# H2_V5_2_schh.net
KiCad netlist of a schematic drawn in EAGLE
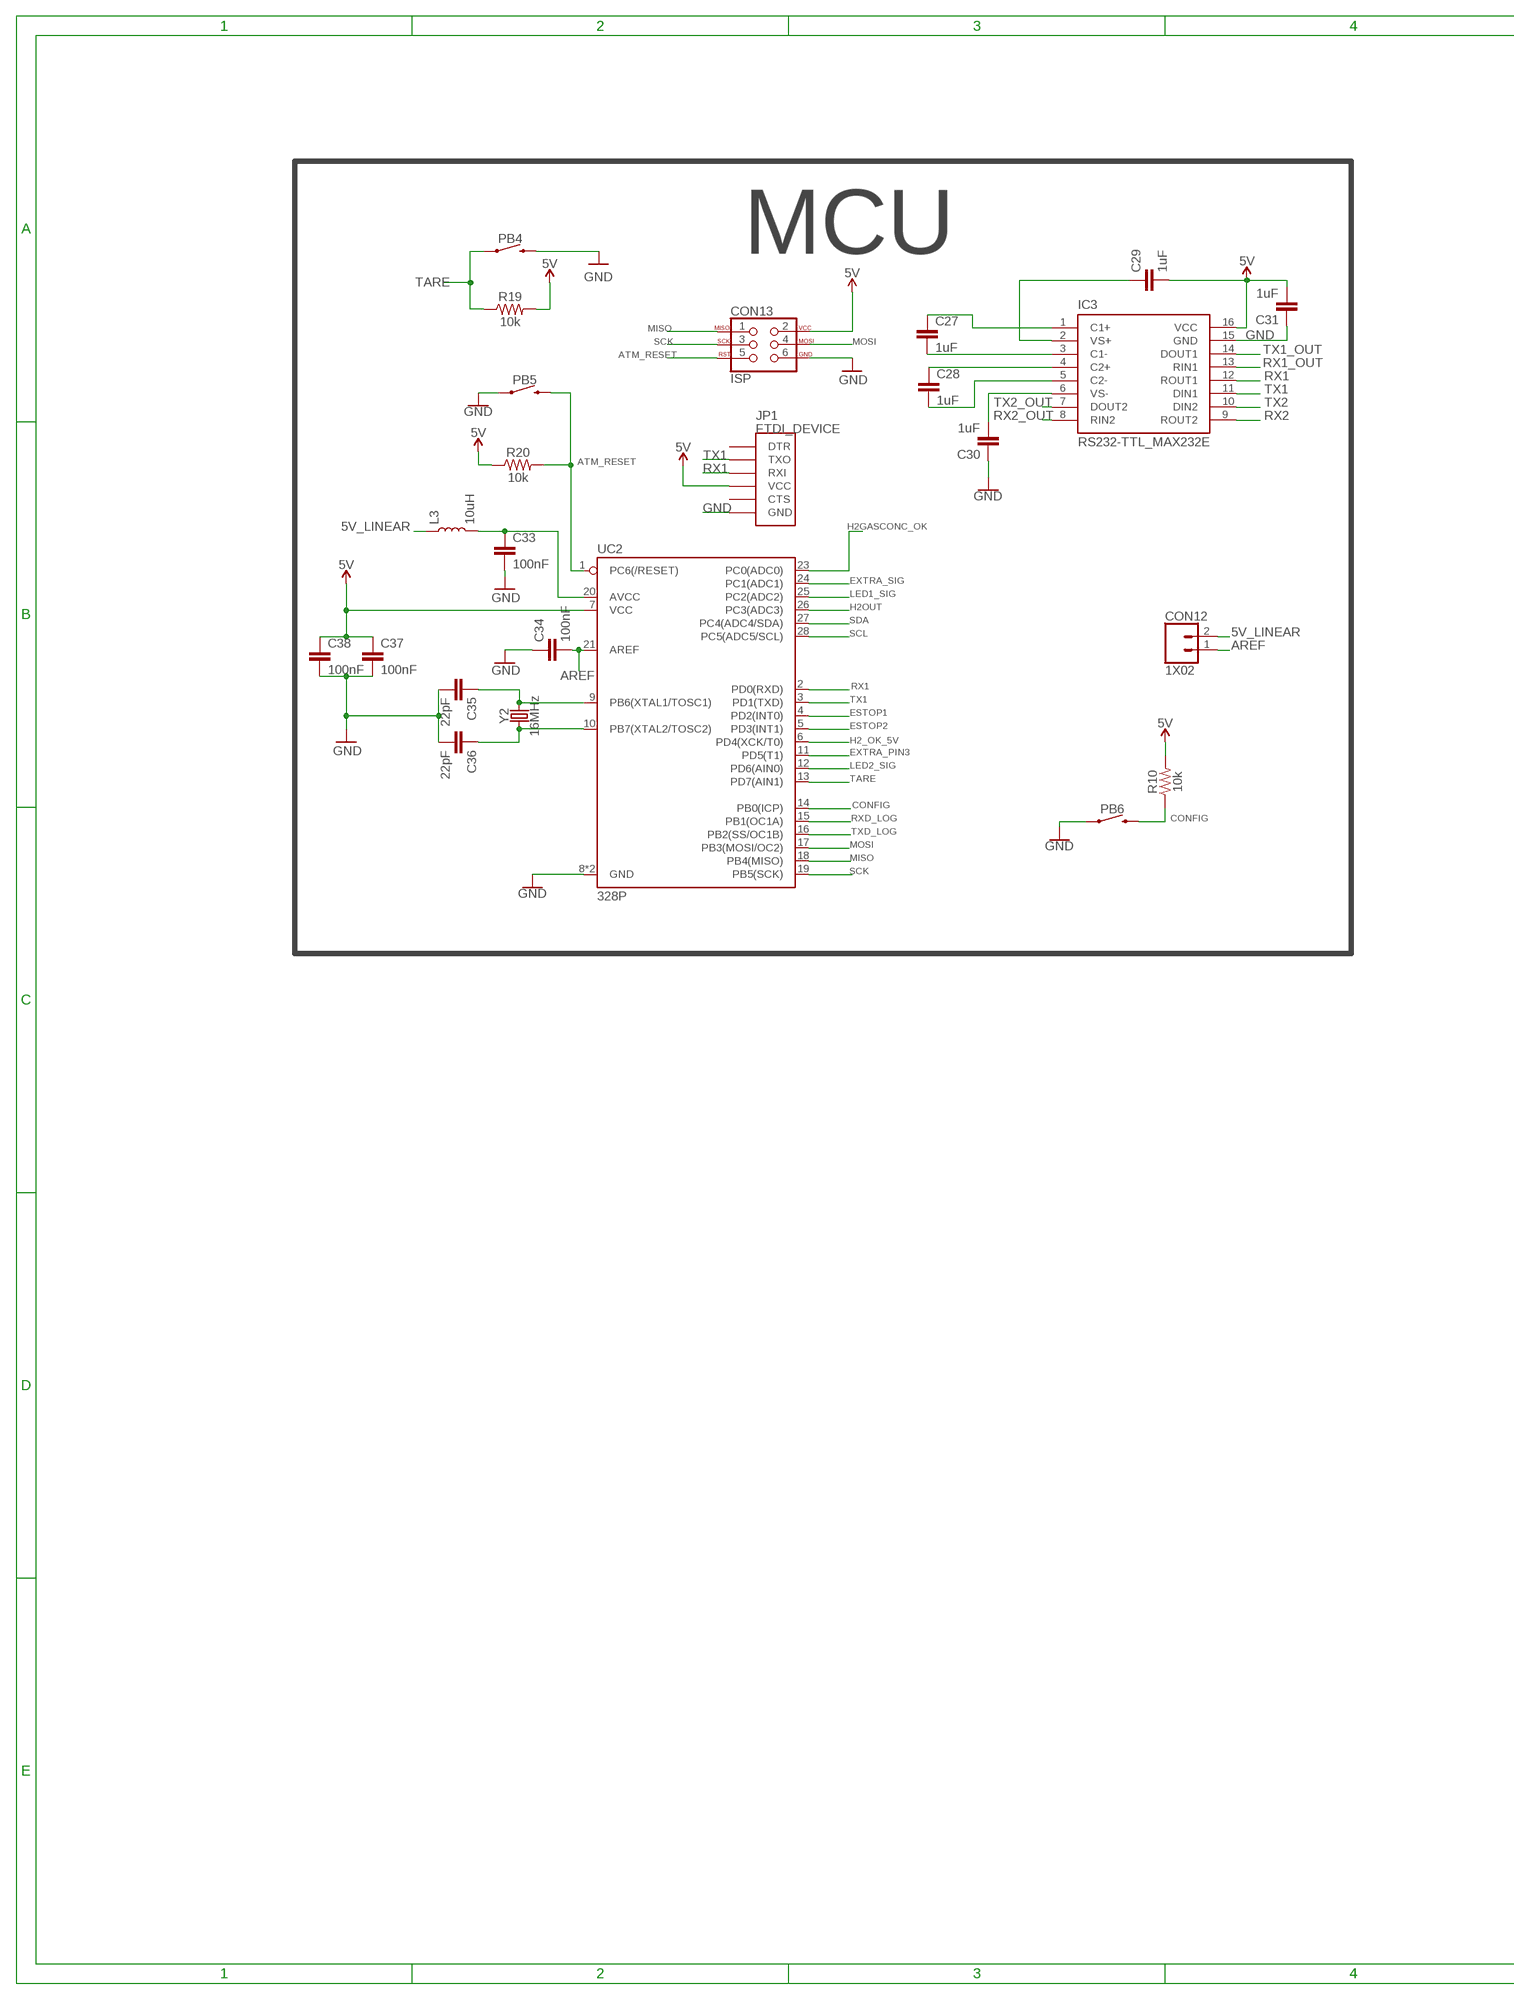
[diagram p0: schematic, sheet 1, part 1 of 2]
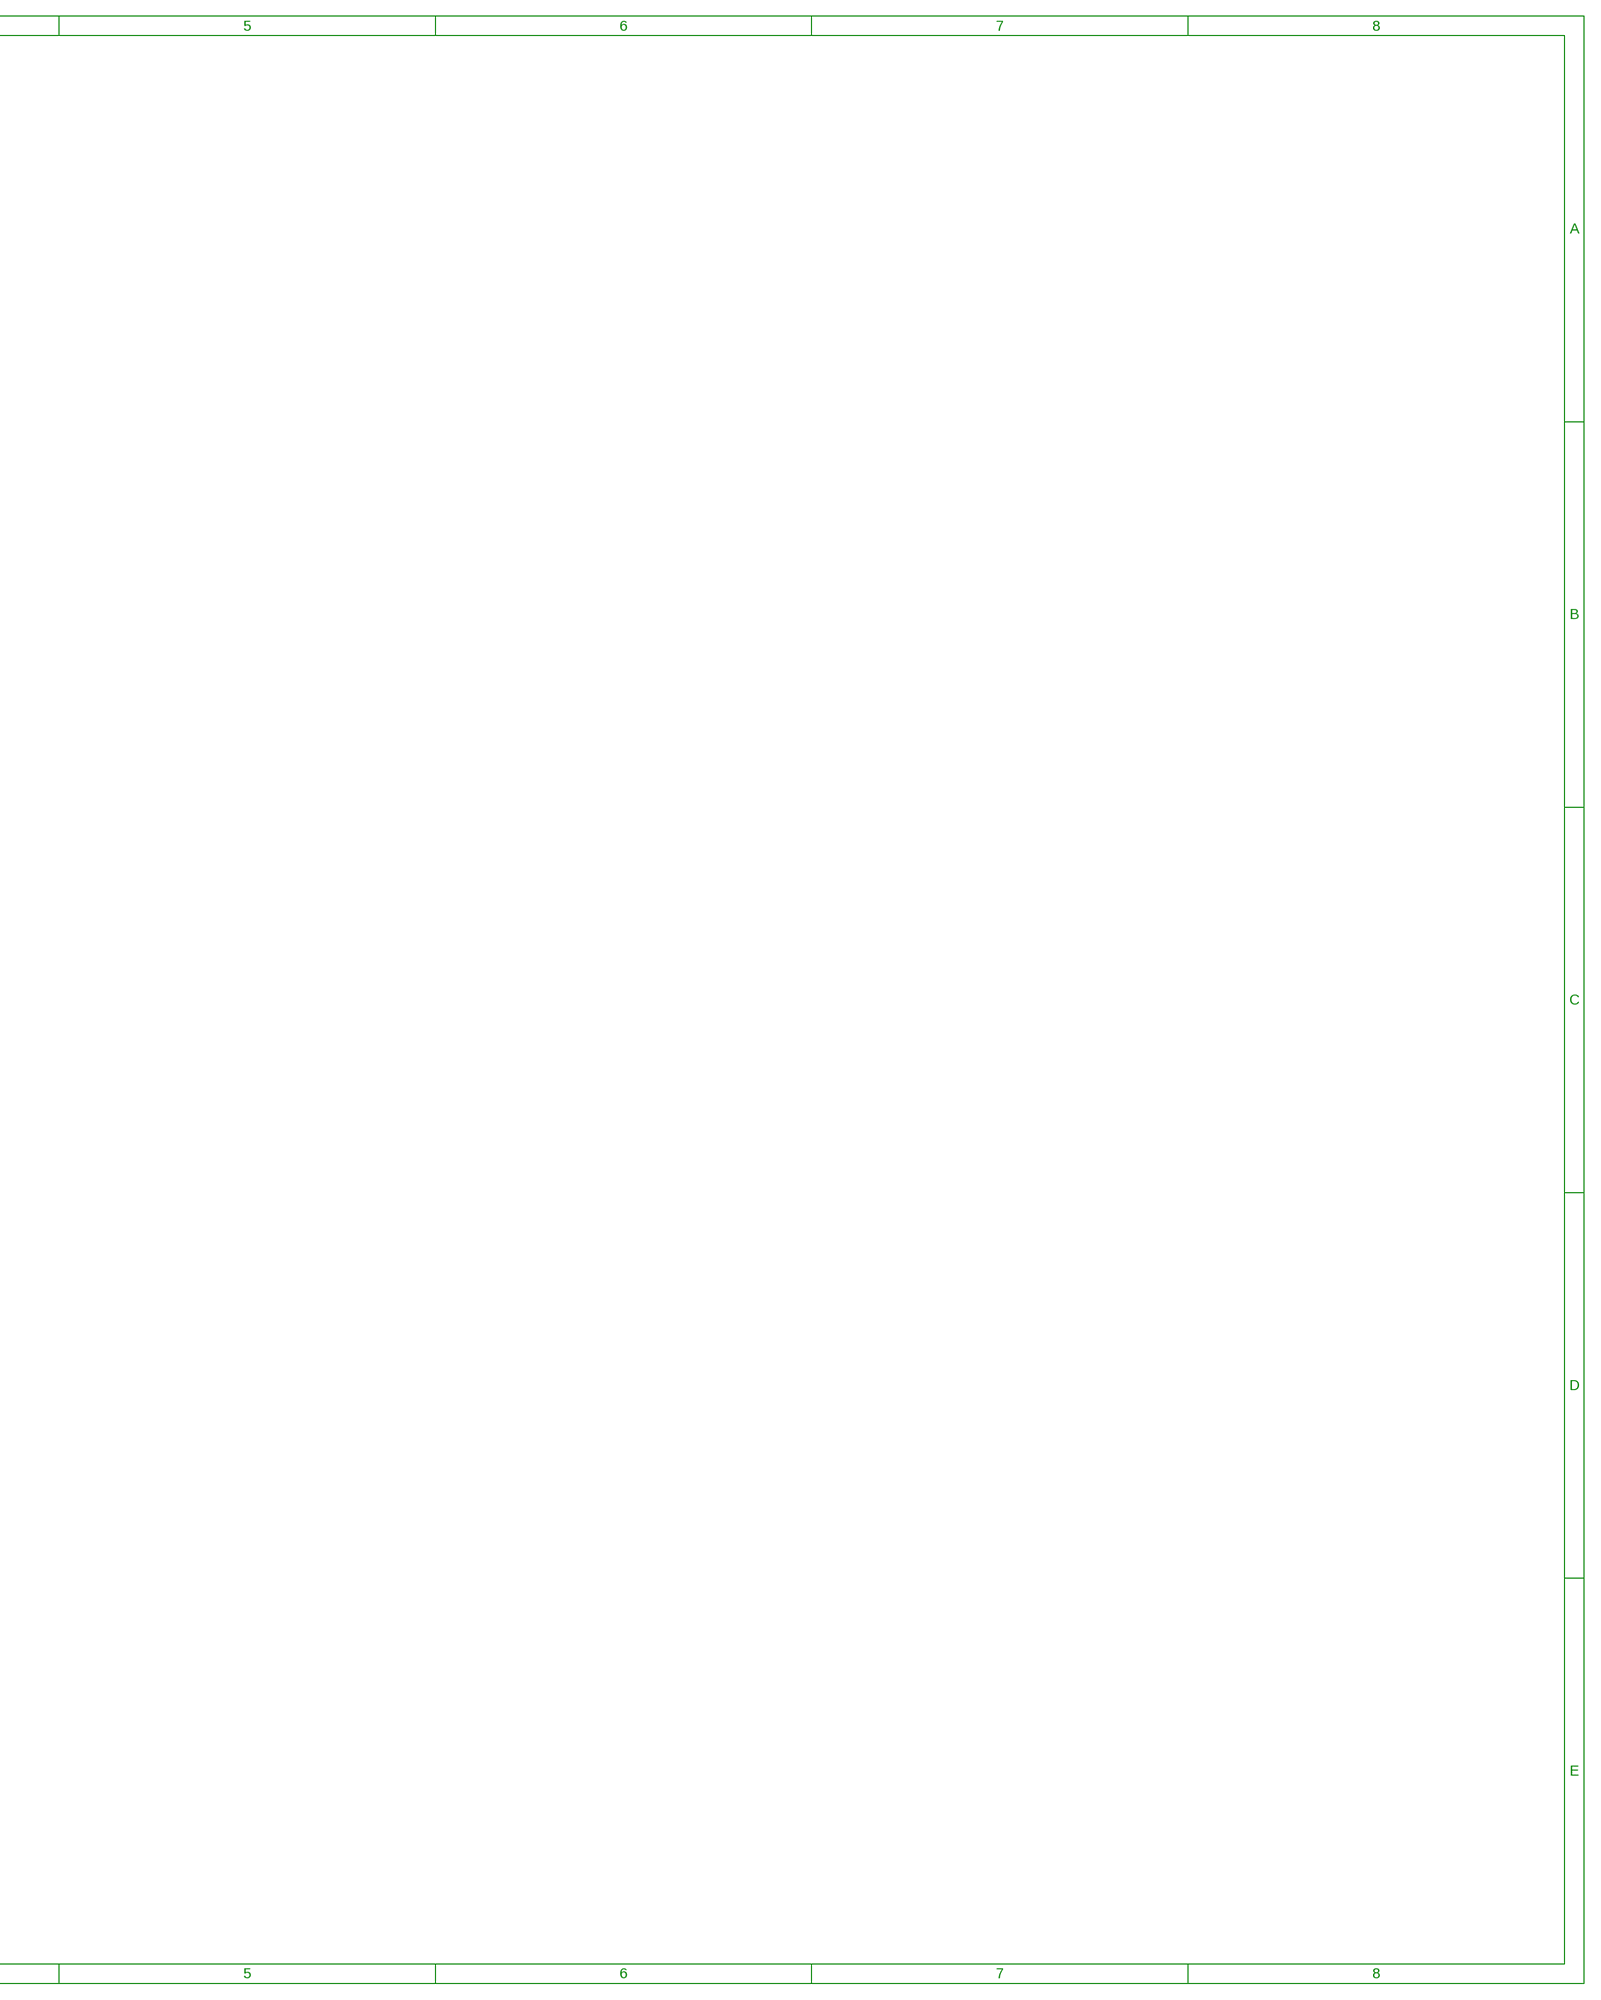
[diagram p1: schematic, sheet 1, part 2 of 2]
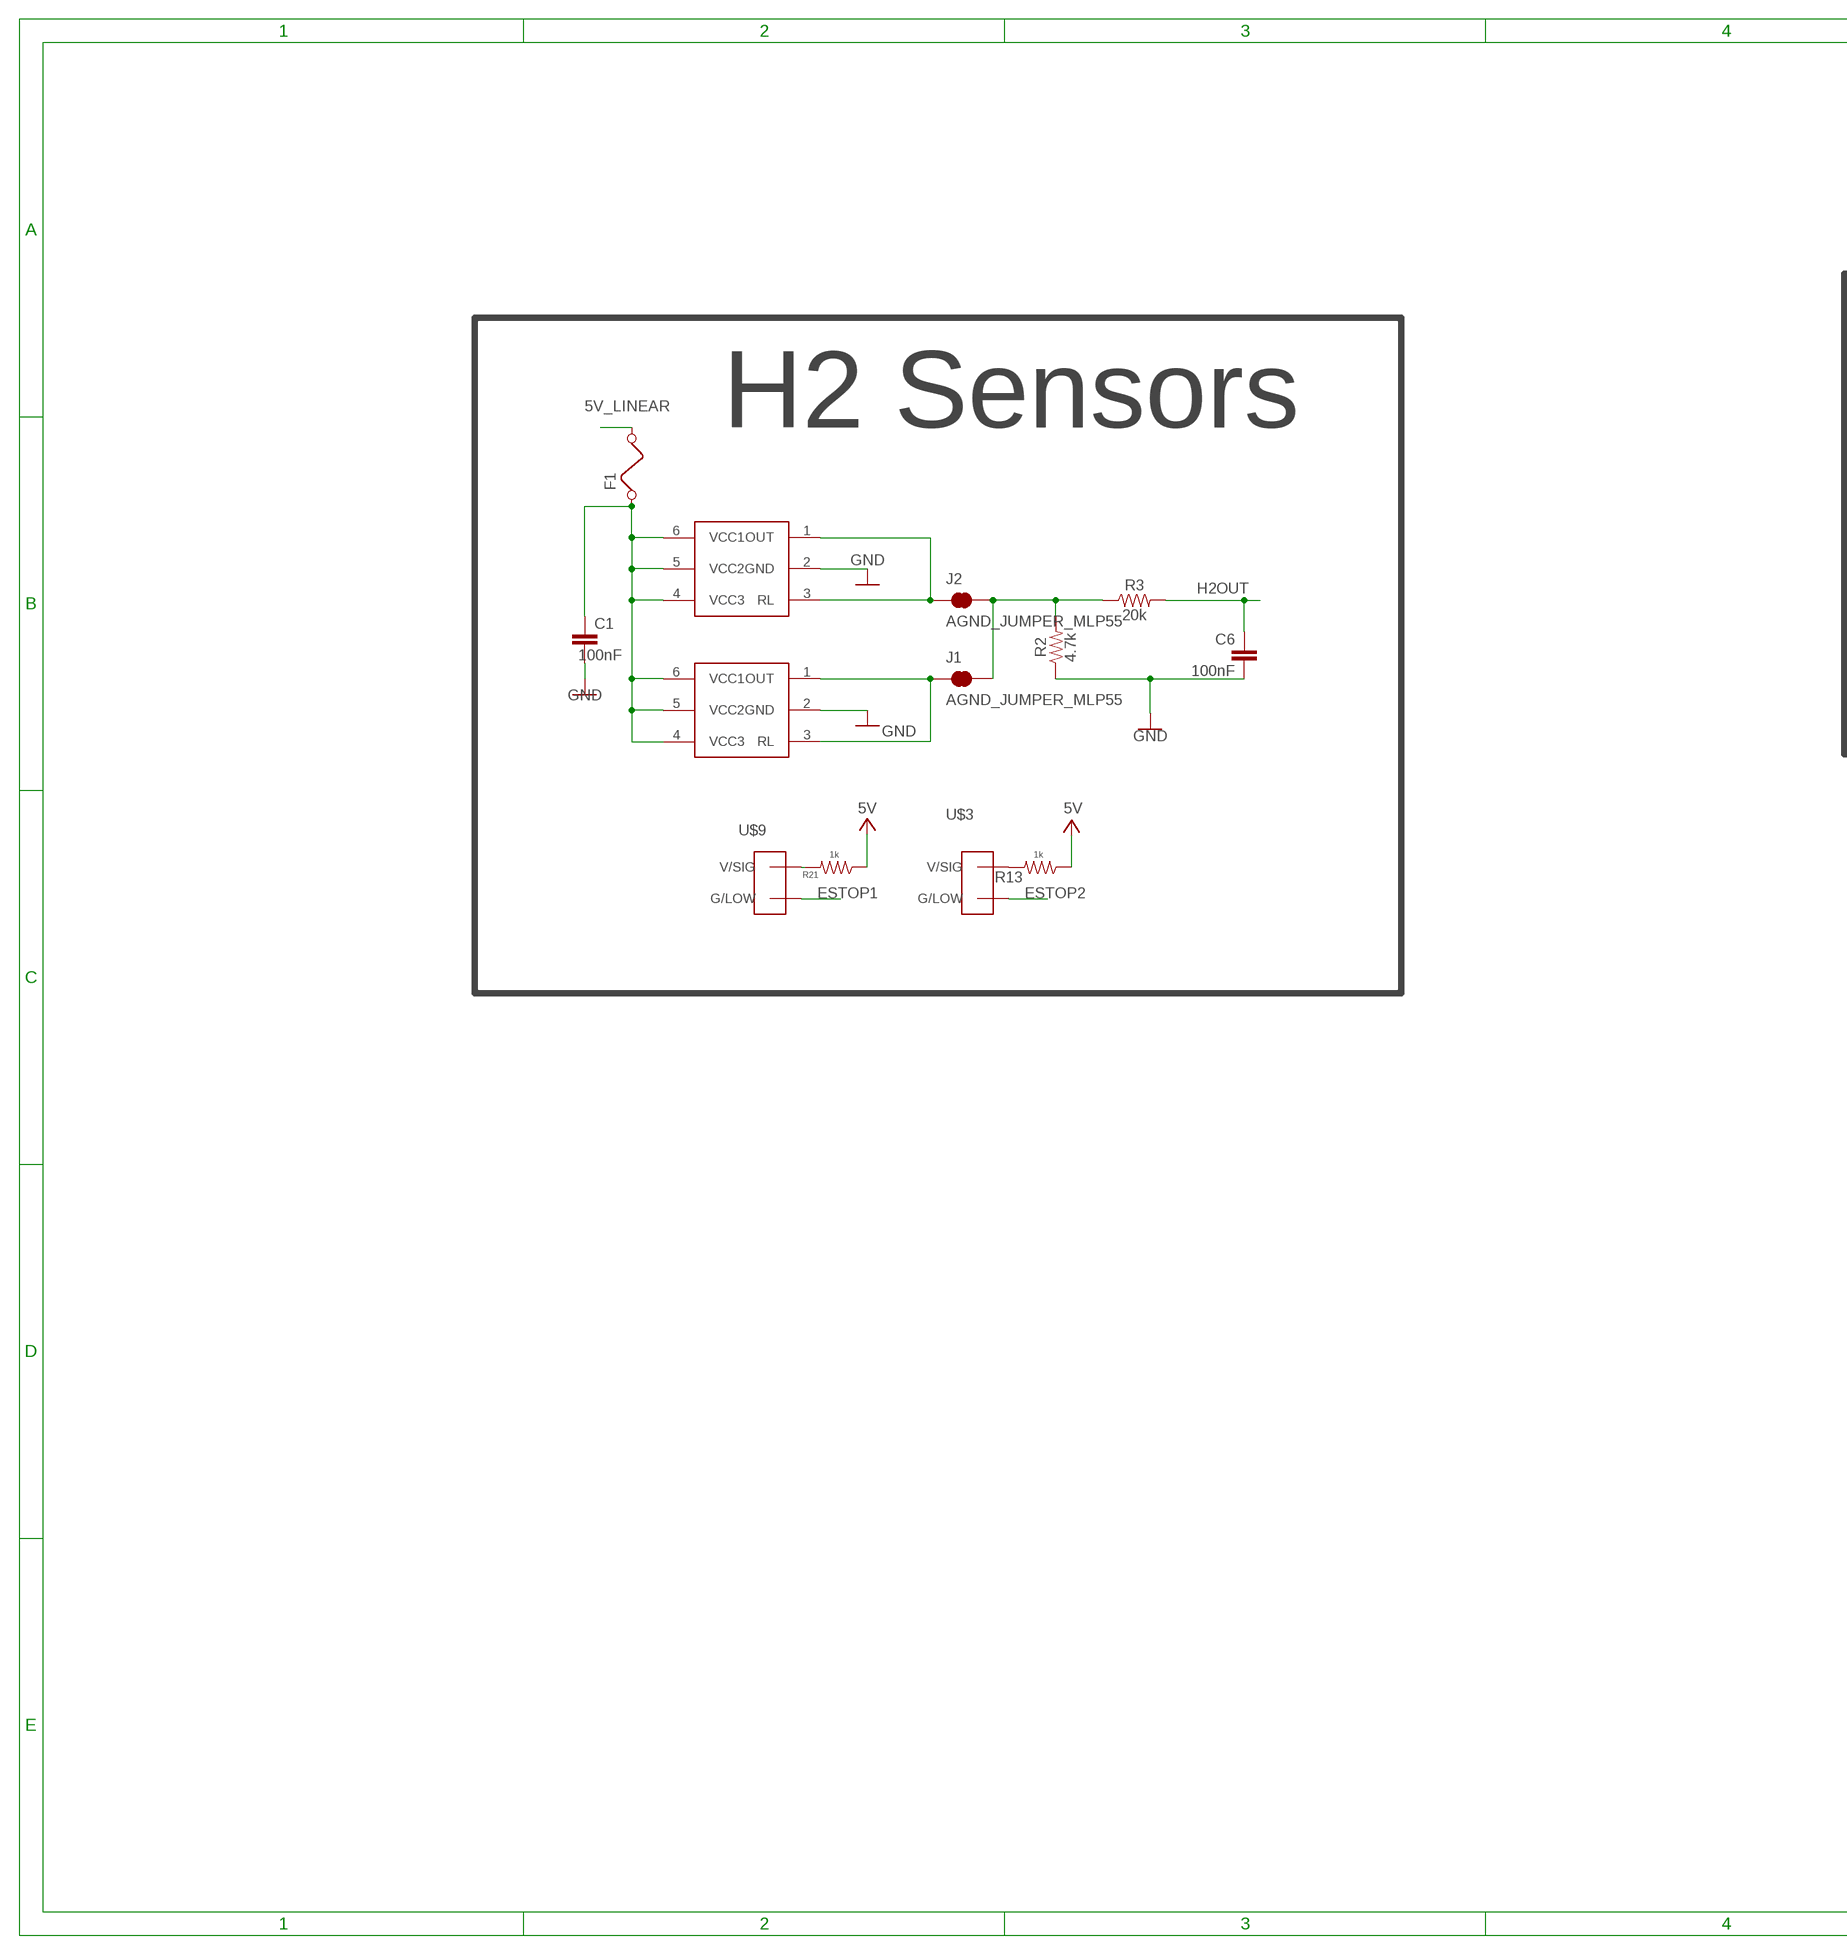
[diagram p2: schematic, sheet 2, part 1 of 2]
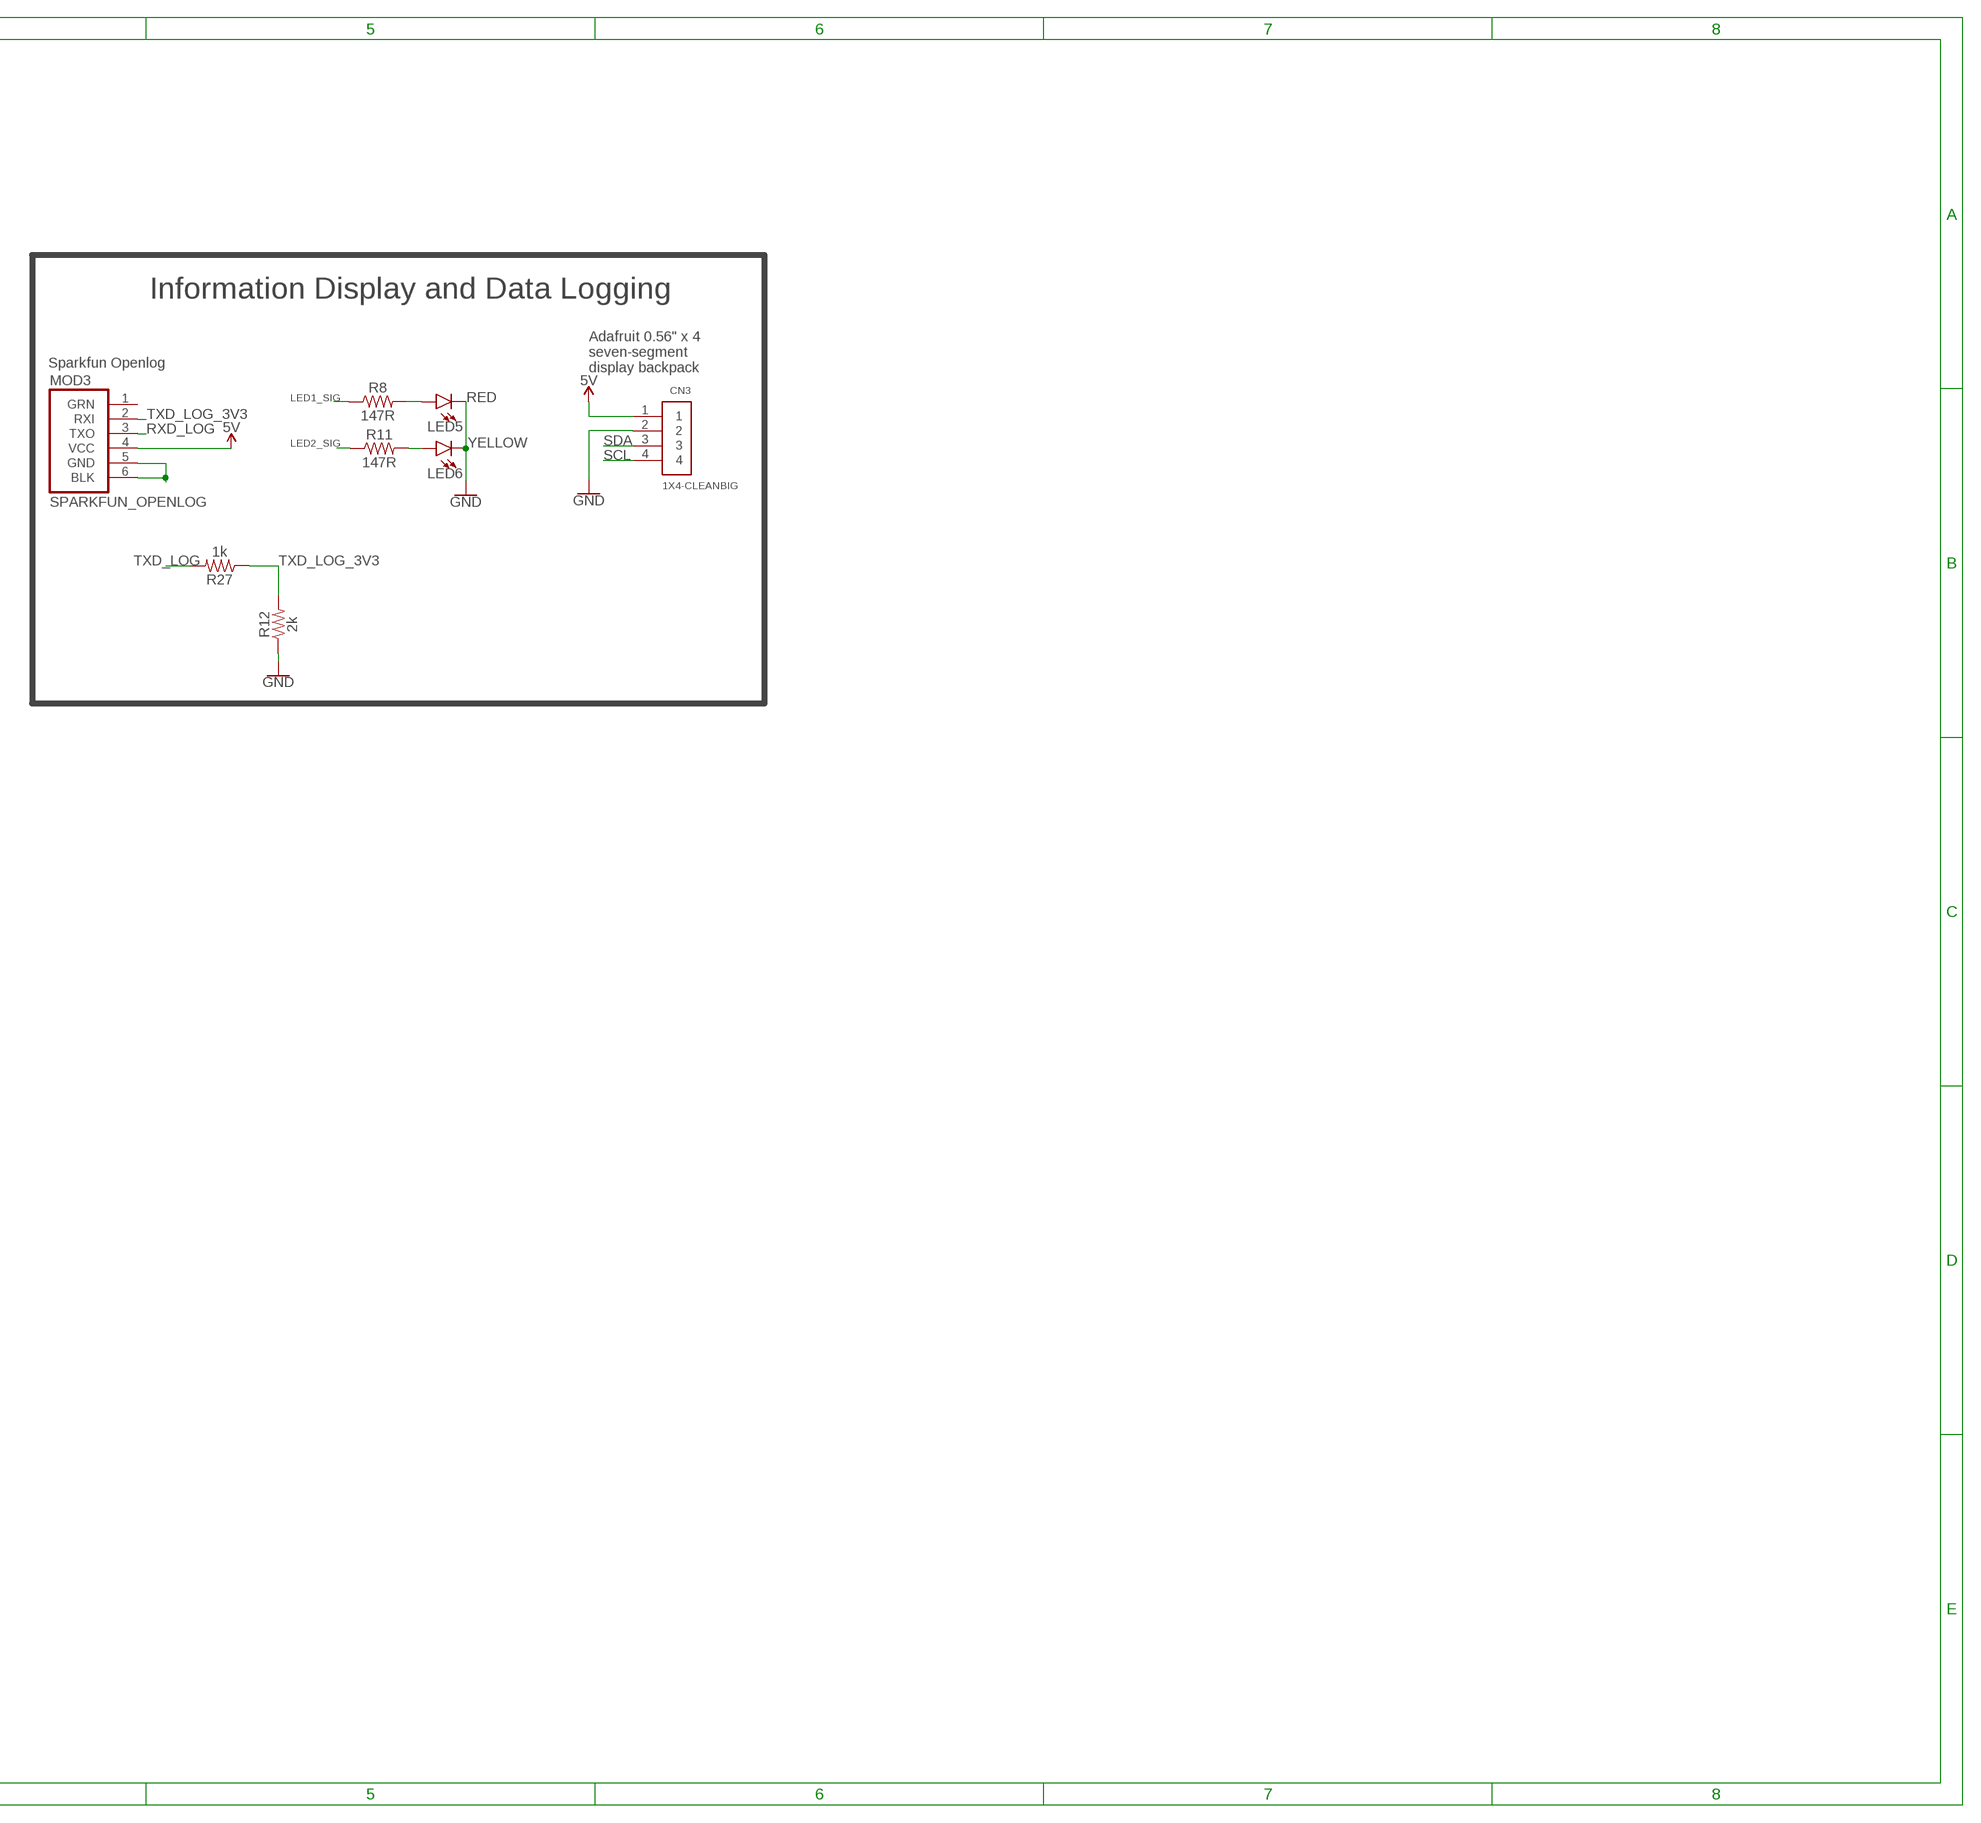
[diagram p3: schematic, sheet 2, part 2 of 2]
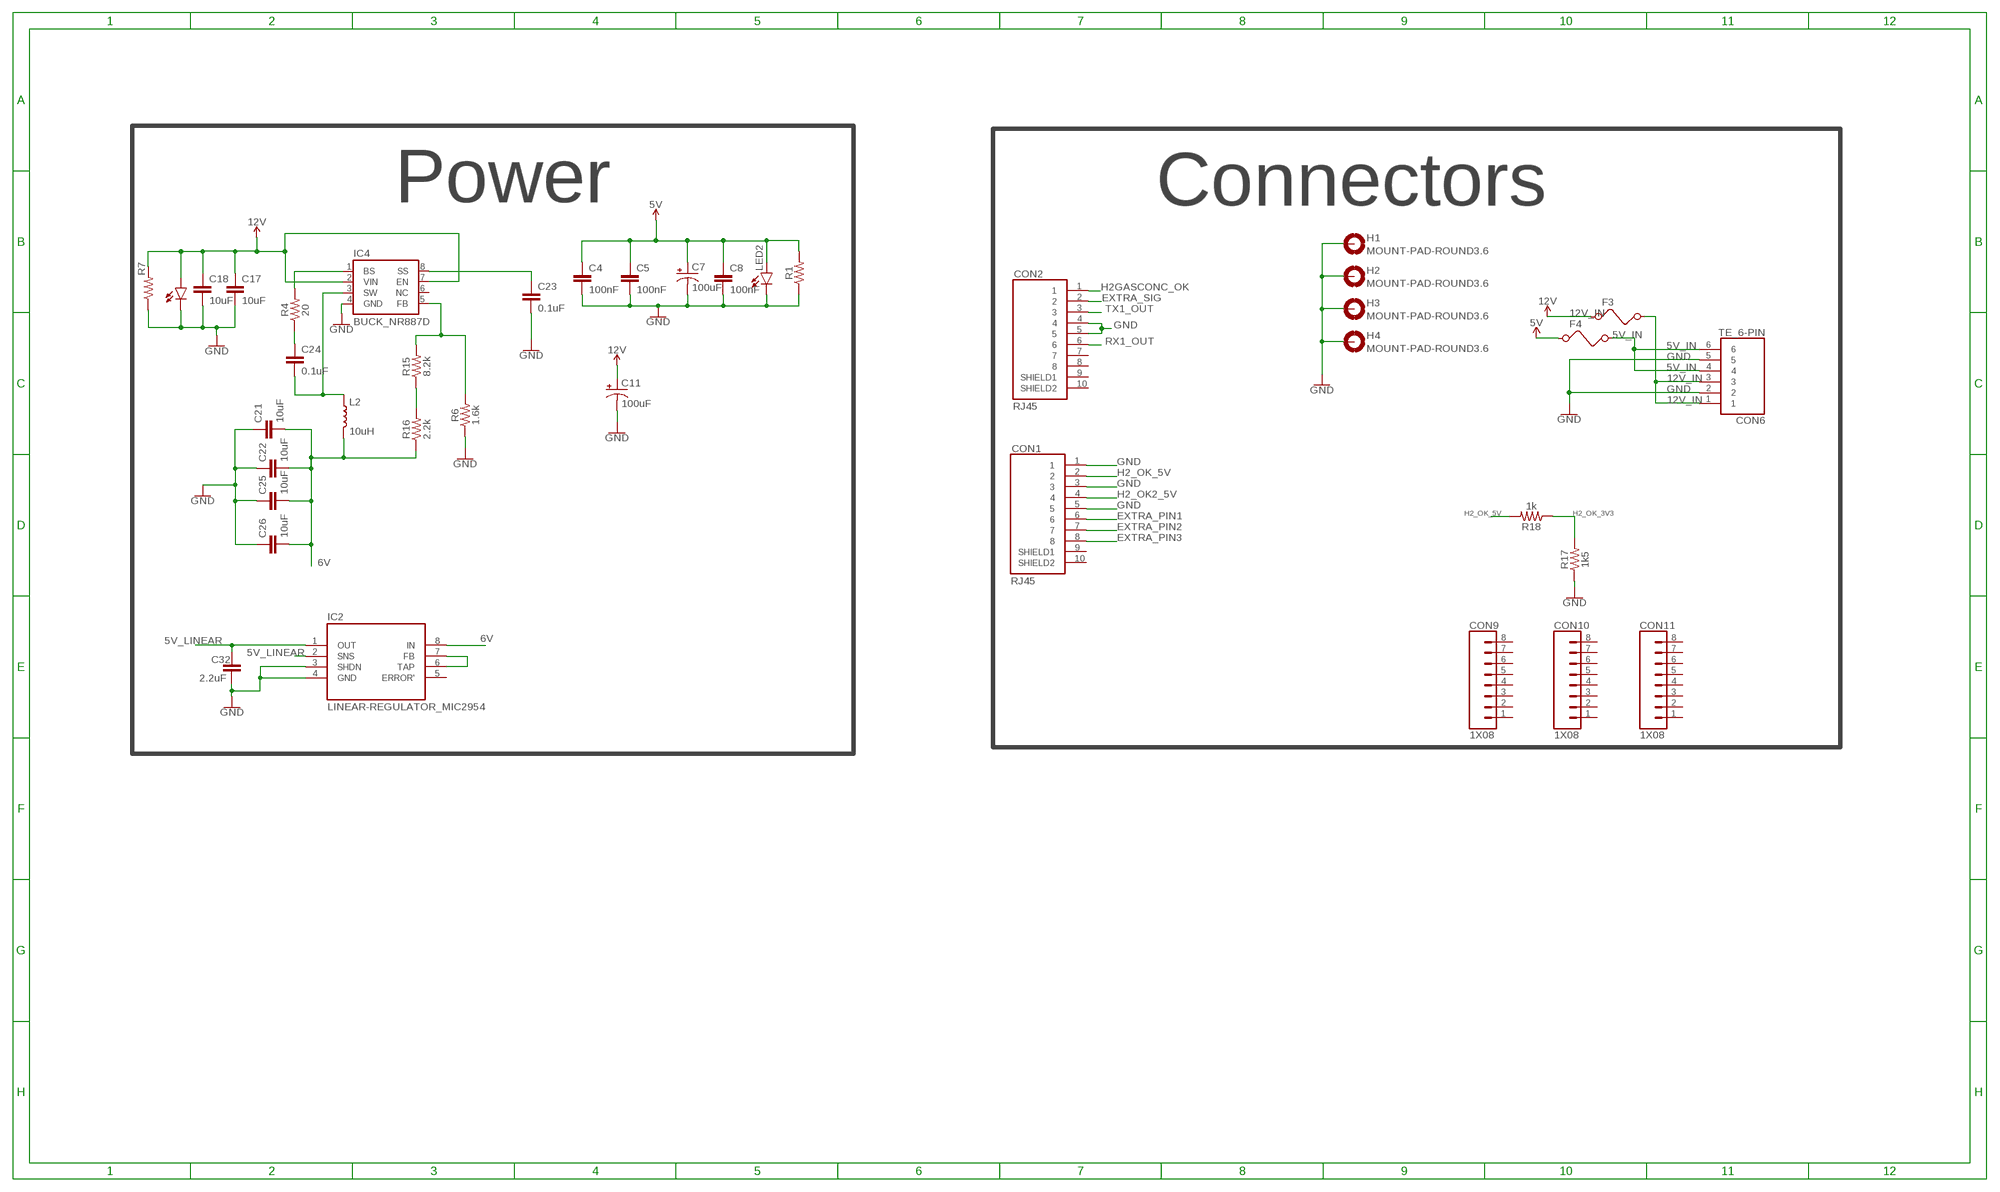
[diagram p4: schematic, sheet 3]

(export (version "E")
  (design (tool "Eeschema 10.0.6"))
  (components
    (comp (ref "C1")
      (value "100nF")
      (footprint "eagle-import:0805")
      (libsource (lib "eagle-import") (part "CAPACITOR_0805"))
    )
    (comp (ref "C6")
      (value "100nF")
      (footprint "eagle-import:0805")
      (libsource (lib "eagle-import") (part "CAPACITOR_0805"))
    )
    (comp (ref "CN3")
      (value "1X4-CLEANBIG")
      (footprint "eagle-import:1X04-CLEANBIG")
      (libsource (lib "eagle-import") (part "1X4-CLEANBIG"))
    )
    (comp (ref "F1")
      (value "FUSE_1210")
      (footprint "eagle-import:1210")
      (libsource (lib "eagle-import") (part "FUSE_1210"))
    )
    (comp (ref "J1")
      (value "AGND_JUMPER_MLP55")
      (footprint "eagle-import:AGND_JUMPER_MLP55")
      (libsource (lib "eagle-import") (part "AGND_JUMPER_MLP55"))
    )
    (comp (ref "J2")
      (value "AGND_JUMPER_MLP55")
      (footprint "eagle-import:AGND_JUMPER_MLP55")
      (libsource (lib "eagle-import") (part "AGND_JUMPER_MLP55"))
    )
    (comp (ref "LED5")
      (value "RED")
      (footprint "eagle-import:0805_LED")
      (libsource (lib "eagle-import") (part "LED_0805"))
    )
    (comp (ref "LED6")
      (value "YELLOW")
      (footprint "eagle-import:0805_LED")
      (libsource (lib "eagle-import") (part "LED_0805"))
    )
    (comp (ref "MOD3")
      (value "SPARKFUN_OPENLOG")
      (footprint "eagle-import:SPARKFUN_OPENLOG")
      (libsource (lib "eagle-import") (part "SPARKFUN_OPENLOG"))
    )
    (comp (ref "R2")
      (value "4.7k")
      (footprint "eagle-import:0805")
      (libsource (lib "eagle-import") (part "RESISTOR_0805"))
    )
    (comp (ref "R3")
      (value "20k")
      (footprint "eagle-import:0805")
      (libsource (lib "eagle-import") (part "RESISTOR_0805"))
    )
    (comp (ref "R8")
      (value "147R")
      (footprint "eagle-import:0805")
      (libsource (lib "eagle-import") (part "RESISTOR_0805"))
    )
    (comp (ref "R11")
      (value "147R")
      (footprint "eagle-import:0805")
      (libsource (lib "eagle-import") (part "RESISTOR_0805"))
    )
    (comp (ref "R12")
      (value "2k")
      (footprint "eagle-import:0805")
      (libsource (lib "eagle-import") (part "RESISTOR_0805"))
    )
    (comp (ref "R13")
      (value "1k")
      (footprint "eagle-import:0603-RES")
      (libsource (lib "eagle-import") (part "RESISTOR0603-RES"))
    )
    (comp (ref "R21")
      (value "1k")
      (footprint "eagle-import:0603-RES")
      (libsource (lib "eagle-import") (part "RESISTOR0603-RES"))
    )
    (comp (ref "R27")
      (value "1k")
      (footprint "eagle-import:0805")
      (libsource (lib "eagle-import") (part "RESISTOR_0805"))
    )
    (comp (ref "U$1")
      (value "MQ-8MQ-8")
      (footprint "eagle-import:MQ-8")
      (libsource (lib "eagle-import") (part "MQ-8MQ-8"))
    )
    (comp (ref "U$2")
      (value "MQ-8MQ-8")
      (footprint "eagle-import:MQ-8")
      (libsource (lib "eagle-import") (part "MQ-8MQ-8"))
    )
    (comp (ref "U$3")
      (value "TE770966")
      (footprint "eagle-import:2X1-MATE-N-LOCK")
      (libsource (lib "eagle-import") (part "TE770966"))
    )
    (comp (ref "U$9")
      (value "TE770966")
      (footprint "eagle-import:2X1-MATE-N-LOCK")
      (libsource (lib "eagle-import") (part "TE770966"))
    )
    (comp (ref "C4")
      (value "100nF")
      (footprint "eagle-import:0805")
      (libsource (lib "eagle-import") (part "CAPACITOR_0805"))
    )
    (comp (ref "C5")
      (value "100nF")
      (footprint "eagle-import:0805")
      (libsource (lib "eagle-import") (part "CAPACITOR_0805"))
    )
    (comp (ref "C7")
      (value "100uF")
      (footprint "eagle-import:CAPACITOR_100UF_50V")
      (libsource (lib "eagle-import") (part "CAPACITOR_ELECTROLYTIC_100UF"))
    )
    (comp (ref "C8")
      (value "100nF")
      (footprint "eagle-import:0805")
      (libsource (lib "eagle-import") (part "CAPACITOR_0805"))
    )
    (comp (ref "C11")
      (value "100uF")
      (footprint "eagle-import:CAPACITOR_100UF_50V")
      (libsource (lib "eagle-import") (part "CAPACITOR_ELECTROLYTIC_100UF"))
    )
    (comp (ref "C17")
      (value "10uF")
      (footprint "eagle-import:0805")
      (libsource (lib "eagle-import") (part "CAPACITOR_0805"))
    )
    (comp (ref "C18")
      (value "10uF")
      (footprint "eagle-import:0805")
      (libsource (lib "eagle-import") (part "CAPACITOR_0805"))
    )
    (comp (ref "C21")
      (value "10uF")
      (footprint "eagle-import:1210")
      (libsource (lib "eagle-import") (part "CAPACITOR_1210"))
    )
    (comp (ref "C22")
      (value "10uF")
      (footprint "eagle-import:1210")
      (libsource (lib "eagle-import") (part "CAPACITOR_1210"))
    )
    (comp (ref "C23")
      (value "0.1uF")
      (footprint "eagle-import:0805")
      (libsource (lib "eagle-import") (part "CAPACITOR_0805"))
    )
    (comp (ref "C24")
      (value "0.1uF")
      (footprint "eagle-import:0805")
      (libsource (lib "eagle-import") (part "CAPACITOR_0805"))
    )
    (comp (ref "C25")
      (value "10uF")
      (footprint "eagle-import:1210")
      (libsource (lib "eagle-import") (part "CAPACITOR_1210"))
    )
    (comp (ref "C26")
      (value "10uF")
      (footprint "eagle-import:1210")
      (libsource (lib "eagle-import") (part "CAPACITOR_1210"))
    )
    (comp (ref "C32")
      (value "2.2uF")
      (footprint "eagle-import:0805")
      (libsource (lib "eagle-import") (part "CAPACITOR_0805"))
    )
    (comp (ref "CON1")
      (value "RJ45")
      (footprint "eagle-import:RJ45")
      (libsource (lib "eagle-import") (part "RJ45"))
    )
    (comp (ref "CON2")
      (value "RJ45")
      (footprint "eagle-import:RJ45")
      (libsource (lib "eagle-import") (part "RJ45"))
    )
    (comp (ref "CON6")
      (value "TE_6-PIN")
      (footprint "eagle-import:TE_6-PIN")
      (libsource (lib "eagle-import") (part "TE_6-PIN"))
    )
    (comp (ref "CON9")
      (value "1X08")
      (footprint "eagle-import:1X08")
      (libsource (lib "eagle-import") (part "1X08"))
    )
    (comp (ref "CON10")
      (value "1X08")
      (footprint "eagle-import:1X08")
      (libsource (lib "eagle-import") (part "1X08"))
    )
    (comp (ref "CON11")
      (value "1X08")
      (footprint "eagle-import:1X08")
      (libsource (lib "eagle-import") (part "1X08"))
    )
    (comp (ref "F3")
      (value "FUSE_1210")
      (footprint "eagle-import:1210")
      (libsource (lib "eagle-import") (part "FUSE_1210"))
    )
    (comp (ref "F4")
      (value "FUSE_1210")
      (footprint "eagle-import:1210")
      (libsource (lib "eagle-import") (part "FUSE_1210"))
    )
    (comp (ref "H1")
      (value "MOUNT-PAD-ROUND3.6")
      (footprint "eagle-import:3,6-PAD")
      (libsource (lib "eagle-import") (part "MOUNT-PAD-ROUND3.6"))
    )
    (comp (ref "H2")
      (value "MOUNT-PAD-ROUND3.6")
      (footprint "eagle-import:3,6-PAD")
      (libsource (lib "eagle-import") (part "MOUNT-PAD-ROUND3.6"))
    )
    (comp (ref "H3")
      (value "MOUNT-PAD-ROUND3.6")
      (footprint "eagle-import:3,6-PAD")
      (libsource (lib "eagle-import") (part "MOUNT-PAD-ROUND3.6"))
    )
    (comp (ref "H4")
      (value "MOUNT-PAD-ROUND3.6")
      (footprint "eagle-import:3,6-PAD")
      (libsource (lib "eagle-import") (part "MOUNT-PAD-ROUND3.6"))
    )
    (comp (ref "IC2")
      (value "LINEAR-REGULATOR_MIC2954")
      (footprint "eagle-import:SOIC8")
      (libsource (lib "eagle-import") (part "LINEAR-REGULATOR_MIC2954"))
    )
    (comp (ref "IC4")
      (value "BUCK_NR887D")
      (footprint "eagle-import:DIP08")
      (libsource (lib "eagle-import") (part "BUCK_NR887D"))
    )
    (comp (ref "L2")
      (value "10uH")
      (footprint "eagle-import:INDUCTOR_MURATA_DEM8030C")
      (libsource (lib "eagle-import") (part "INDUCTOR_MURATA_DEM8030C"))
    )
    (comp (ref "LED1")
      (value "LED_0805")
      (footprint "eagle-import:0805_LED")
      (libsource (lib "eagle-import") (part "LED_0805"))
    )
    (comp (ref "LED2")
      (value "LED_0805")
      (footprint "eagle-import:0805_LED")
      (libsource (lib "eagle-import") (part "LED_0805"))
    )
    (comp (ref "R1")
      (value "RESISTOR_0805")
      (footprint "eagle-import:0805")
      (libsource (lib "eagle-import") (part "RESISTOR_0805"))
    )
    (comp (ref "R4")
      (value "20")
      (footprint "eagle-import:0805")
      (libsource (lib "eagle-import") (part "RESISTOR_0805"))
    )
    (comp (ref "R6")
      (value "1.6k")
      (footprint "eagle-import:0805")
      (libsource (lib "eagle-import") (part "RESISTOR_0805"))
    )
    (comp (ref "R7")
      (value "RESISTOR_0805")
      (footprint "eagle-import:0805")
      (libsource (lib "eagle-import") (part "RESISTOR_0805"))
    )
    (comp (ref "R15")
      (value "8.2k")
      (footprint "eagle-import:0805")
      (libsource (lib "eagle-import") (part "RESISTOR_0805"))
    )
    (comp (ref "R16")
      (value "2.2k")
      (footprint "eagle-import:0805")
      (libsource (lib "eagle-import") (part "RESISTOR_0805"))
    )
    (comp (ref "R17")
      (value "1k5")
      (footprint "eagle-import:0805")
      (libsource (lib "eagle-import") (part "RESISTOR_0805"))
    )
    (comp (ref "R18")
      (value "1k")
      (footprint "eagle-import:0805")
      (libsource (lib "eagle-import") (part "RESISTOR_0805"))
    )
    (comp (ref "C27")
      (value "1uF")
      (footprint "eagle-import:0805")
      (libsource (lib "eagle-import") (part "CAPACITOR_0805"))
    )
    (comp (ref "C28")
      (value "1uF")
      (footprint "eagle-import:0805")
      (libsource (lib "eagle-import") (part "CAPACITOR_0805"))
    )
    (comp (ref "C29")
      (value "1uF")
      (footprint "eagle-import:0805")
      (libsource (lib "eagle-import") (part "CAPACITOR_0805"))
    )
    (comp (ref "C30")
      (value "1uF")
      (footprint "eagle-import:0805")
      (libsource (lib "eagle-import") (part "CAPACITOR_0805"))
    )
    (comp (ref "C31")
      (value "1uF")
      (footprint "eagle-import:0805")
      (libsource (lib "eagle-import") (part "CAPACITOR_0805"))
    )
    (comp (ref "C33")
      (value "100nF")
      (footprint "eagle-import:0805")
      (libsource (lib "eagle-import") (part "CAPACITOR_0805"))
    )
    (comp (ref "C34")
      (value "100nF")
      (footprint "eagle-import:0805")
      (libsource (lib "eagle-import") (part "CAPACITOR_0805"))
    )
    (comp (ref "C35")
      (value "22pF")
      (footprint "eagle-import:0805")
      (libsource (lib "eagle-import") (part "CAPACITOR_0805"))
    )
    (comp (ref "C36")
      (value "22pF")
      (footprint "eagle-import:0805")
      (libsource (lib "eagle-import") (part "CAPACITOR_0805"))
    )
    (comp (ref "C37")
      (value "100nF")
      (footprint "eagle-import:0805")
      (libsource (lib "eagle-import") (part "CAPACITOR_0805"))
    )
    (comp (ref "C38")
      (value "100nF")
      (footprint "eagle-import:0805")
      (libsource (lib "eagle-import") (part "CAPACITOR_0805"))
    )
    (comp (ref "CON12")
      (value "1X02")
      (footprint "eagle-import:1X02")
      (libsource (lib "eagle-import") (part "1X02"))
    )
    (comp (ref "CON13")
      (value "ISP")
      (footprint "eagle-import:ISP_CONNECTOR")
      (libsource (lib "eagle-import") (part "ISP"))
    )
    (comp (ref "IC3")
      (value "RS232-TTL_MAX232E")
      (footprint "eagle-import:DIP16")
      (libsource (lib "eagle-import") (part "RS232-TTL_MAX232E"))
    )
    (comp (ref "JP1")
      (value "FTDI_DEVICE")
      (footprint "eagle-import:FTDI_DEVICE_SIDE")
      (libsource (lib "eagle-import") (part "FTDI_DEVICE"))
    )
    (comp (ref "L3")
      (value "10uH")
      (footprint "eagle-import:0805")
      (libsource (lib "eagle-import") (part "INDUCTOR_0805"))
    )
    (comp (ref "PB4")
      (value "PUSHBUTTON")
      (footprint "eagle-import:PUSHBUTTON")
      (libsource (lib "eagle-import") (part "PUSHBUTTON"))
    )
    (comp (ref "PB5")
      (value "PUSHBUTTON")
      (footprint "eagle-import:PUSHBUTTON")
      (libsource (lib "eagle-import") (part "PUSHBUTTON"))
    )
    (comp (ref "PB6")
      (value "PUSHBUTTON")
      (footprint "eagle-import:PUSHBUTTON")
      (libsource (lib "eagle-import") (part "PUSHBUTTON"))
    )
    (comp (ref "R10")
      (value "10k")
      (footprint "eagle-import:0805")
      (libsource (lib "eagle-import") (part "RESISTOR_0805"))
    )
    (comp (ref "R19")
      (value "10k")
      (footprint "eagle-import:0805")
      (libsource (lib "eagle-import") (part "RESISTOR_0805"))
    )
    (comp (ref "R20")
      (value "10k")
      (footprint "eagle-import:0805")
      (libsource (lib "eagle-import") (part "RESISTOR_0805"))
    )
    (comp (ref "UC2")
      (value "328P")
      (footprint "eagle-import:DIP28")
      (libsource (lib "eagle-import") (part "ATMEGA328P_DIP28"))
    )
    (comp (ref "Y2")
      (value "16MHz")
      (footprint "eagle-import:HC49US")
      (libsource (lib "eagle-import") (part "CRYSTAL-16MHZPTH-HC49US"))
    )
  )
  (nets
    (net (code "1") (name "5V") (class "Default")
      (node (ref "C29") (pin "2") (pinfunction "2_2") (pintype "passive"))
      (node (ref "C31") (pin "2") (pinfunction "2_2") (pintype "passive"))
      (node (ref "C37") (pin "1") (pinfunction "1_1") (pintype "passive"))
      (node (ref "C38") (pin "1") (pinfunction "1_1") (pintype "passive"))
      (node (ref "C4") (pin "1") (pinfunction "1_1") (pintype "passive"))
      (node (ref "C5") (pin "1") (pinfunction "1_1") (pintype "passive"))
      (node (ref "C7") (pin "+") (pinfunction "+_+") (pintype "passive"))
      (node (ref "C8") (pin "1") (pinfunction "1_1") (pintype "passive"))
      (node (ref "CN3") (pin "1") (pinfunction "1_1") (pintype "bidirectional"))
      (node (ref "CON13") (pin "2") (pinfunction "2_2") (pintype "passive"))
      (node (ref "F4") (pin "1") (pinfunction "1_1") (pintype "passive"))
      (node (ref "IC3") (pin "16") (pinfunction "VCC_16") (pintype "bidirectional"))
      (node (ref "JP1") (pin "P$4") (pinfunction "VCC_P$4") (pintype "bidirectional"))
      (node (ref "LED2") (pin "1") (pinfunction "A_1") (pintype "passive"))
      (node (ref "MOD3") (pin "4") (pinfunction "VCC_4") (pintype "passive"))
      (node (ref "R1") (pin "2") (pinfunction "2_2") (pintype "passive"))
      (node (ref "R10") (pin "2") (pinfunction "2_2") (pintype "passive"))
      (node (ref "R13") (pin "1") (pinfunction "1_1") (pintype "passive"))
      (node (ref "R19") (pin "2") (pinfunction "2_2") (pintype "passive"))
      (node (ref "R20") (pin "1") (pinfunction "1_1") (pintype "passive"))
      (node (ref "R21") (pin "1") (pinfunction "1_1") (pintype "passive"))
      (node (ref "UC2") (pin "7") (pinfunction "VCC_7") (pintype "bidirectional"))
    )
    (net (code "2") (name "5V_IN") (class "Default")
      (node (ref "CON6") (pin "4") (pinfunction "4_4") (pintype "passive"))
      (node (ref "CON6") (pin "6") (pinfunction "6_6") (pintype "passive"))
      (node (ref "F4") (pin "2") (pinfunction "2_2") (pintype "passive"))
    )
    (net (code "3") (name "5V_LINEAR") (class "Default")
      (node (ref "C1") (pin "1") (pinfunction "1_1") (pintype "passive"))
      (node (ref "C32") (pin "1") (pinfunction "1_1") (pintype "passive"))
      (node (ref "CON12") (pin "2") (pinfunction "2_2") (pintype "passive"))
      (node (ref "F1") (pin "1") (pinfunction "1_1") (pintype "passive"))
      (node (ref "F1") (pin "2") (pinfunction "2_2") (pintype "passive"))
      (node (ref "IC2") (pin "1") (pinfunction "OUT_1") (pintype "bidirectional"))
      (node (ref "IC2") (pin "2") (pinfunction "SNS_2") (pintype "bidirectional"))
      (node (ref "L3") (pin "1") (pinfunction "1_1") (pintype "passive"))
      (node (ref "U$1") (pin "4") (pinfunction "VCC3_4") (pintype "bidirectional"))
      (node (ref "U$1") (pin "5") (pinfunction "VCC2_5") (pintype "bidirectional"))
      (node (ref "U$1") (pin "6") (pinfunction "VCC1_6") (pintype "bidirectional"))
      (node (ref "U$2") (pin "4") (pinfunction "VCC3_4") (pintype "bidirectional"))
      (node (ref "U$2") (pin "5") (pinfunction "VCC2_5") (pintype "bidirectional"))
      (node (ref "U$2") (pin "6") (pinfunction "VCC1_6") (pintype "bidirectional"))
    )
    (net (code "4") (name "6V") (class "Default")
      (node (ref "C21") (pin "2") (pinfunction "2_2") (pintype "passive"))
      (node (ref "C22") (pin "2") (pinfunction "2_2") (pintype "passive"))
      (node (ref "C25") (pin "2") (pinfunction "2_2") (pintype "passive"))
      (node (ref "C26") (pin "2") (pinfunction "2_2") (pintype "passive"))
      (node (ref "IC2") (pin "8") (pinfunction "IN_8") (pintype "bidirectional"))
      (node (ref "L2") (pin "P$2") (pinfunction "2_P$2") (pintype "passive"))
      (node (ref "R16") (pin "1") (pinfunction "1_1") (pintype "passive"))
    )
    (net (code "5") (name "12V") (class "Default")
      (node (ref "C11") (pin "+") (pinfunction "+_+") (pintype "passive"))
      (node (ref "C17") (pin "1") (pinfunction "1_1") (pintype "passive"))
      (node (ref "C18") (pin "1") (pinfunction "1_1") (pintype "passive"))
      (node (ref "F3") (pin "1") (pinfunction "1_1") (pintype "passive"))
      (node (ref "IC4") (pin "2") (pinfunction "VIN_2") (pintype "bidirectional"))
      (node (ref "IC4") (pin "7") (pinfunction "EN_7") (pintype "bidirectional"))
      (node (ref "LED1") (pin "1") (pinfunction "A_1") (pintype "passive"))
      (node (ref "R7") (pin "2") (pinfunction "2_2") (pintype "passive"))
    )
    (net (code "6") (name "12V_IN") (class "Default")
      (node (ref "CON6") (pin "1") (pinfunction "1_1") (pintype "passive"))
      (node (ref "CON6") (pin "3") (pinfunction "3_3") (pintype "passive"))
      (node (ref "F3") (pin "2") (pinfunction "2_2") (pintype "passive"))
    )
    (net (code "7") (name "AREF") (class "Default")
      (node (ref "C34") (pin "2") (pinfunction "2_2") (pintype "passive"))
      (node (ref "CON12") (pin "1") (pinfunction "1_1") (pintype "passive"))
      (node (ref "UC2") (pin "21") (pinfunction "AREF_21") (pintype "bidirectional"))
    )
    (net (code "8") (name "ATM_RESET") (class "Default")
      (node (ref "CON13") (pin "5") (pinfunction "5_5") (pintype "passive"))
      (node (ref "PB5") (pin "3") (pinfunction "2_3") (pintype "passive"))
      (node (ref "PB5") (pin "4") (pinfunction "2_4") (pintype "passive"))
      (node (ref "R20") (pin "2") (pinfunction "2_2") (pintype "passive"))
      (node (ref "UC2") (pin "1") (pinfunction "PC6(/RESET)_1") (pintype "bidirectional"))
    )
    (net (code "9") (name "CONFIG") (class "Default")
      (node (ref "PB6") (pin "3") (pinfunction "2_3") (pintype "passive"))
      (node (ref "PB6") (pin "4") (pinfunction "2_4") (pintype "passive"))
      (node (ref "R10") (pin "1") (pinfunction "1_1") (pintype "passive"))
      (node (ref "UC2") (pin "14") (pinfunction "PB0(ICP)_14") (pintype "bidirectional"))
    )
    (net (code "10") (name "ESTOP1") (class "Default")
      (node (ref "U$9") (pin "CIRCUIT2") (pinfunction "G/LOW_CIRCUIT2") (pintype "bidirectional"))
      (node (ref "UC2") (pin "4") (pinfunction "PD2(INT0)_4") (pintype "bidirectional"))
    )
    (net (code "11") (name "ESTOP2") (class "Default")
      (node (ref "U$3") (pin "CIRCUIT2") (pinfunction "G/LOW_CIRCUIT2") (pintype "bidirectional"))
      (node (ref "UC2") (pin "5") (pinfunction "PD3(INT1)_5") (pintype "bidirectional"))
    )
    (net (code "12") (name "EXTRA_PIN1") (class "Default")
      (node (ref "CON1") (pin "6") (pinfunction "6_6") (pintype "passive"))
    )
    (net (code "13") (name "EXTRA_PIN2") (class "Default")
      (node (ref "CON1") (pin "7") (pinfunction "7_7") (pintype "passive"))
    )
    (net (code "14") (name "EXTRA_PIN3") (class "Default")
      (node (ref "CON1") (pin "8") (pinfunction "8_8") (pintype "passive"))
      (node (ref "UC2") (pin "11") (pinfunction "PD5(T1)_11") (pintype "bidirectional"))
    )
    (net (code "15") (name "EXTRA_SIG") (class "Default")
      (node (ref "CON2") (pin "2") (pinfunction "2_2") (pintype "passive"))
      (node (ref "UC2") (pin "24") (pinfunction "PC1(ADC1)_24") (pintype "bidirectional"))
    )
    (net (code "16") (name "GND") (class "Default")
      (node (ref "C1") (pin "2") (pinfunction "2_2") (pintype "passive"))
      (node (ref "C11") (pin "-") (pinfunction "-_-") (pintype "passive"))
      (node (ref "C17") (pin "2") (pinfunction "2_2") (pintype "passive"))
      (node (ref "C18") (pin "2") (pinfunction "2_2") (pintype "passive"))
      (node (ref "C21") (pin "1") (pinfunction "1_1") (pintype "passive"))
      (node (ref "C22") (pin "1") (pinfunction "1_1") (pintype "passive"))
      (node (ref "C23") (pin "2") (pinfunction "2_2") (pintype "passive"))
      (node (ref "C25") (pin "1") (pinfunction "1_1") (pintype "passive"))
      (node (ref "C26") (pin "1") (pinfunction "1_1") (pintype "passive"))
      (node (ref "C30") (pin "1") (pinfunction "1_1") (pintype "passive"))
      (node (ref "C31") (pin "1") (pinfunction "1_1") (pintype "passive"))
      (node (ref "C32") (pin "2") (pinfunction "2_2") (pintype "passive"))
      (node (ref "C33") (pin "2") (pinfunction "2_2") (pintype "passive"))
      (node (ref "C34") (pin "1") (pinfunction "1_1") (pintype "passive"))
      (node (ref "C35") (pin "2") (pinfunction "2_2") (pintype "passive"))
      (node (ref "C36") (pin "2") (pinfunction "2_2") (pintype "passive"))
      (node (ref "C37") (pin "2") (pinfunction "2_2") (pintype "passive"))
      (node (ref "C38") (pin "2") (pinfunction "2_2") (pintype "passive"))
      (node (ref "C4") (pin "2") (pinfunction "2_2") (pintype "passive"))
      (node (ref "C5") (pin "2") (pinfunction "2_2") (pintype "passive"))
      (node (ref "C6") (pin "2") (pinfunction "2_2") (pintype "passive"))
      (node (ref "C7") (pin "-") (pinfunction "-_-") (pintype "passive"))
      (node (ref "C8") (pin "2") (pinfunction "2_2") (pintype "passive"))
      (node (ref "CN3") (pin "2") (pinfunction "2_2") (pintype "bidirectional"))
      (node (ref "CON1") (pin "1") (pinfunction "1_1") (pintype "passive"))
      (node (ref "CON1") (pin "3") (pinfunction "3_3") (pintype "passive"))
      (node (ref "CON1") (pin "5") (pinfunction "5_5") (pintype "passive"))
      (node (ref "CON13") (pin "6") (pinfunction "6_6") (pintype "passive"))
      (node (ref "CON2") (pin "4") (pinfunction "4_4") (pintype "passive"))
      (node (ref "CON2") (pin "5") (pinfunction "5_5") (pintype "passive"))
      (node (ref "CON6") (pin "2") (pinfunction "2_2") (pintype "passive"))
      (node (ref "CON6") (pin "5") (pinfunction "5_5") (pintype "passive"))
      (node (ref "H1") (pin "B3,6") (pinfunction "MOUNT_B3,6") (pintype "passive"))
      (node (ref "H2") (pin "B3,6") (pinfunction "MOUNT_B3,6") (pintype "passive"))
      (node (ref "H3") (pin "B3,6") (pinfunction "MOUNT_B3,6") (pintype "passive"))
      (node (ref "H4") (pin "B3,6") (pinfunction "MOUNT_B3,6") (pintype "passive"))
      (node (ref "IC2") (pin "3") (pinfunction "SHDN_3") (pintype "bidirectional"))
      (node (ref "IC2") (pin "4") (pinfunction "GND_4") (pintype "bidirectional"))
      (node (ref "IC3") (pin "15") (pinfunction "GND_15") (pintype "bidirectional"))
      (node (ref "IC4") (pin "4") (pinfunction "GND_4") (pintype "bidirectional"))
      (node (ref "JP1") (pin "P$6") (pinfunction "GND_P$6") (pintype "bidirectional"))
      (node (ref "LED1") (pin "2") (pinfunction "C_2") (pintype "passive"))
      (node (ref "LED2") (pin "2") (pinfunction "C_2") (pintype "passive"))
      (node (ref "LED5") (pin "2") (pinfunction "C_2") (pintype "passive"))
      (node (ref "LED6") (pin "2") (pinfunction "C_2") (pintype "passive"))
      (node (ref "PB4") (pin "3") (pinfunction "2_3") (pintype "passive"))
      (node (ref "PB4") (pin "4") (pinfunction "2_4") (pintype "passive"))
      (node (ref "PB5") (pin "1") (pinfunction "1_1") (pintype "passive"))
      (node (ref "PB5") (pin "2") (pinfunction "1_2") (pintype "passive"))
      (node (ref "PB6") (pin "1") (pinfunction "1_1") (pintype "passive"))
      (node (ref "PB6") (pin "2") (pinfunction "1_2") (pintype "passive"))
      (node (ref "R1") (pin "1") (pinfunction "1_1") (pintype "passive"))
      (node (ref "R12") (pin "1") (pinfunction "1_1") (pintype "passive"))
      (node (ref "R17") (pin "1") (pinfunction "1_1") (pintype "passive"))
      (node (ref "R2") (pin "1") (pinfunction "1_1") (pintype "passive"))
      (node (ref "R6") (pin "1") (pinfunction "1_1") (pintype "passive"))
      (node (ref "R7") (pin "1") (pinfunction "1_1") (pintype "passive"))
      (node (ref "U$1") (pin "2") (pinfunction "GND_2") (pintype "bidirectional"))
      (node (ref "U$2") (pin "2") (pinfunction "GND_2") (pintype "bidirectional"))
      (node (ref "UC2") (pin "22") (pinfunction "GND_22") (pintype "bidirectional"))
      (node (ref "UC2") (pin "8") (pinfunction "GND_8") (pintype "bidirectional"))
    )
    (net (code "17") (name "H2GASCONC_OK") (class "Default")
      (node (ref "CON2") (pin "1") (pinfunction "1_1") (pintype "passive"))
      (node (ref "UC2") (pin "23") (pinfunction "PC0(ADC0)_23") (pintype "bidirectional"))
    )
    (net (code "18") (name "H2OUT") (class "Default")
      (node (ref "C6") (pin "1") (pinfunction "1_1") (pintype "passive"))
      (node (ref "R3") (pin "2") (pinfunction "2_2") (pintype "passive"))
      (node (ref "UC2") (pin "26") (pinfunction "PC3(ADC3)_26") (pintype "bidirectional"))
    )
    (net (code "19") (name "H2_OK2_5V") (class "Default")
      (node (ref "CON1") (pin "4") (pinfunction "4_4") (pintype "passive"))
    )
    (net (code "20") (name "H2_OK_3V3") (class "Default")
      (node (ref "R17") (pin "2") (pinfunction "2_2") (pintype "passive"))
      (node (ref "R18") (pin "1") (pinfunction "1_1") (pintype "passive"))
    )
    (net (code "21") (name "H2_OK_5V") (class "Default")
      (node (ref "CON1") (pin "2") (pinfunction "2_2") (pintype "passive"))
      (node (ref "R18") (pin "2") (pinfunction "2_2") (pintype "passive"))
      (node (ref "UC2") (pin "6") (pinfunction "PD4(XCK/T0)_6") (pintype "bidirectional"))
    )
    (net (code "22") (name "LED1_SIG") (class "Default")
      (node (ref "R8") (pin "1") (pinfunction "1_1") (pintype "passive"))
      (node (ref "UC2") (pin "25") (pinfunction "PC2(ADC2)_25") (pintype "bidirectional"))
    )
    (net (code "23") (name "LED2_SIG") (class "Default")
      (node (ref "R11") (pin "1") (pinfunction "1_1") (pintype "passive"))
      (node (ref "UC2") (pin "12") (pinfunction "PD6(AIN0)_12") (pintype "bidirectional"))
    )
    (net (code "24") (name "MISO") (class "Default")
      (node (ref "CON13") (pin "1") (pinfunction "1_1") (pintype "passive"))
      (node (ref "UC2") (pin "18") (pinfunction "PB4(MISO)_18") (pintype "bidirectional"))
    )
    (net (code "25") (name "MOSI") (class "Default")
      (node (ref "CON13") (pin "4") (pinfunction "4_4") (pintype "passive"))
      (node (ref "UC2") (pin "17") (pinfunction "PB3(MOSI/OC2)_17") (pintype "bidirectional"))
    )
    (net (code "26") (name "Net-(C24-Pad1)") (class "Default")
      (node (ref "C24") (pin "1") (pinfunction "1_1") (pintype "passive"))
      (node (ref "R4") (pin "1") (pinfunction "1_1") (pintype "passive"))
    )
    (net (code "27") (name "Net-(IC2-FB)") (class "Default")
      (node (ref "IC2") (pin "6") (pinfunction "TAP_6") (pintype "bidirectional"))
      (node (ref "IC2") (pin "7") (pinfunction "FB_7") (pintype "bidirectional"))
    )
    (net (code "28") (name "Net-(IC3-C1+)") (class "Default")
      (node (ref "C27") (pin "1") (pinfunction "1_1") (pintype "passive"))
      (node (ref "IC3") (pin "1") (pinfunction "C1+_1") (pintype "bidirectional"))
    )
    (net (code "29") (name "Net-(IC3-C1-)") (class "Default")
      (node (ref "C27") (pin "2") (pinfunction "2_2") (pintype "passive"))
      (node (ref "IC3") (pin "3") (pinfunction "C1-_3") (pintype "bidirectional"))
    )
    (net (code "30") (name "Net-(IC3-C2+)") (class "Default")
      (node (ref "C28") (pin "1") (pinfunction "1_1") (pintype "passive"))
      (node (ref "IC3") (pin "4") (pinfunction "C2+_4") (pintype "bidirectional"))
    )
    (net (code "31") (name "Net-(IC3-C2-)") (class "Default")
      (node (ref "C28") (pin "2") (pinfunction "2_2") (pintype "passive"))
      (node (ref "IC3") (pin "5") (pinfunction "C2-_5") (pintype "bidirectional"))
    )
    (net (code "32") (name "Net-(IC3-VS+)") (class "Default")
      (node (ref "C29") (pin "1") (pinfunction "1_1") (pintype "passive"))
      (node (ref "IC3") (pin "2") (pinfunction "VS+_2") (pintype "bidirectional"))
    )
    (net (code "33") (name "Net-(IC3-VS-)") (class "Default")
      (node (ref "C30") (pin "2") (pinfunction "2_2") (pintype "passive"))
      (node (ref "IC3") (pin "6") (pinfunction "VS-_6") (pintype "bidirectional"))
    )
    (net (code "34") (name "Net-(IC4-BS)") (class "Default")
      (node (ref "IC4") (pin "1") (pinfunction "BS_1") (pintype "bidirectional"))
      (node (ref "R4") (pin "2") (pinfunction "2_2") (pintype "passive"))
    )
    (net (code "35") (name "Net-(IC4-FB)") (class "Default")
      (node (ref "IC4") (pin "5") (pinfunction "FB_5") (pintype "bidirectional"))
      (node (ref "R15") (pin "2") (pinfunction "2_2") (pintype "passive"))
      (node (ref "R6") (pin "2") (pinfunction "2_2") (pintype "passive"))
    )
    (net (code "36") (name "Net-(IC4-SS)") (class "Default")
      (node (ref "C23") (pin "1") (pinfunction "1_1") (pintype "passive"))
      (node (ref "IC4") (pin "8") (pinfunction "SS_8") (pintype "bidirectional"))
    )
    (net (code "37") (name "Net-(IC4-SW)") (class "Default")
      (node (ref "C24") (pin "2") (pinfunction "2_2") (pintype "passive"))
      (node (ref "IC4") (pin "3") (pinfunction "SW_3") (pintype "bidirectional"))
      (node (ref "L2") (pin "P$1") (pinfunction "1_P$1") (pintype "passive"))
    )
    (net (code "38") (name "Net-(J1-1)") (class "Default")
      (node (ref "J1") (pin "P$1") (pinfunction "1_P$1") (pintype "passive"))
      (node (ref "U$2") (pin "1") (pinfunction "OUT_1") (pintype "bidirectional"))
      (node (ref "U$2") (pin "3") (pinfunction "RL_3") (pintype "bidirectional"))
    )
    (net (code "39") (name "Net-(J1-2)") (class "Default")
      (node (ref "J1") (pin "P$2") (pinfunction "2_P$2") (pintype "passive"))
      (node (ref "J2") (pin "P$2") (pinfunction "2_P$2") (pintype "passive"))
      (node (ref "R2") (pin "2") (pinfunction "2_2") (pintype "passive"))
      (node (ref "R3") (pin "1") (pinfunction "1_1") (pintype "passive"))
    )
    (net (code "40") (name "Net-(J2-1)") (class "Default")
      (node (ref "J2") (pin "P$1") (pinfunction "1_P$1") (pintype "passive"))
      (node (ref "U$1") (pin "1") (pinfunction "OUT_1") (pintype "bidirectional"))
      (node (ref "U$1") (pin "3") (pinfunction "RL_3") (pintype "bidirectional"))
    )
    (net (code "41") (name "Net-(LED5-A)") (class "Default")
      (node (ref "LED5") (pin "1") (pinfunction "A_1") (pintype "passive"))
      (node (ref "R8") (pin "2") (pinfunction "2_2") (pintype "passive"))
    )
    (net (code "42") (name "Net-(LED6-A)") (class "Default")
      (node (ref "LED6") (pin "1") (pinfunction "A_1") (pintype "passive"))
      (node (ref "R11") (pin "2") (pinfunction "2_2") (pintype "passive"))
    )
    (net (code "43") (name "Net-(MOD3-BLK)") (class "Default")
      (node (ref "MOD3") (pin "5") (pinfunction "GND_5") (pintype "passive"))
      (node (ref "MOD3") (pin "6") (pinfunction "BLK_6") (pintype "passive"))
    )
    (net (code "44") (name "Net-(R15-Pad1)") (class "Default")
      (node (ref "R15") (pin "1") (pinfunction "1_1") (pintype "passive"))
      (node (ref "R16") (pin "2") (pinfunction "2_2") (pintype "passive"))
    )
    (net (code "45") (name "Net-(U$3-V{slash}SIG)") (class "Default")
      (node (ref "R13") (pin "2") (pinfunction "2_2") (pintype "passive"))
      (node (ref "U$3") (pin "CIRCUIT1") (pinfunction "V/SIG_CIRCUIT1") (pintype "bidirectional"))
    )
    (net (code "46") (name "Net-(U$9-V{slash}SIG)") (class "Default")
      (node (ref "R21") (pin "2") (pinfunction "2_2") (pintype "passive"))
      (node (ref "U$9") (pin "CIRCUIT1") (pinfunction "V/SIG_CIRCUIT1") (pintype "bidirectional"))
    )
    (net (code "47") (name "Net-(UC2-AVCC)") (class "Default")
      (node (ref "C33") (pin "1") (pinfunction "1_1") (pintype "passive"))
      (node (ref "L3") (pin "2") (pinfunction "2_2") (pintype "passive"))
      (node (ref "UC2") (pin "20") (pinfunction "AVCC_20") (pintype "bidirectional"))
    )
    (net (code "48") (name "Net-(UC2-PB6(XTAL1{slash}TOSC1))") (class "Default")
      (node (ref "C35") (pin "1") (pinfunction "1_1") (pintype "passive"))
      (node (ref "UC2") (pin "9") (pinfunction "PB6(XTAL1/TOSC1)_9") (pintype "bidirectional"))
      (node (ref "Y2") (pin "2") (pinfunction "2_2") (pintype "passive"))
    )
    (net (code "49") (name "Net-(UC2-PB7(XTAL2{slash}TOSC2))") (class "Default")
      (node (ref "C36") (pin "1") (pinfunction "1_1") (pintype "passive"))
      (node (ref "UC2") (pin "10") (pinfunction "PB7(XTAL2/TOSC2)_10") (pintype "bidirectional"))
      (node (ref "Y2") (pin "1") (pinfunction "1_1") (pintype "passive"))
    )
    (net (code "50") (name "RX1") (class "Default")
      (node (ref "IC3") (pin "12") (pinfunction "ROUT1_12") (pintype "bidirectional"))
      (node (ref "JP1") (pin "P$3") (pinfunction "RXI_P$3") (pintype "bidirectional"))
      (node (ref "UC2") (pin "2") (pinfunction "PD0(RXD)_2") (pintype "bidirectional"))
    )
    (net (code "51") (name "RX1_OUT") (class "Default")
      (node (ref "CON2") (pin "6") (pinfunction "6_6") (pintype "passive"))
      (node (ref "IC3") (pin "13") (pinfunction "RIN1_13") (pintype "bidirectional"))
    )
    (net (code "52") (name "RX2") (class "Default")
      (node (ref "IC3") (pin "9") (pinfunction "ROUT2_9") (pintype "bidirectional"))
    )
    (net (code "53") (name "RX2_OUT") (class "Default")
      (node (ref "IC3") (pin "8") (pinfunction "RIN2_8") (pintype "bidirectional"))
    )
    (net (code "54") (name "RXD_LOG") (class "Default")
      (node (ref "MOD3") (pin "3") (pinfunction "TXO_3") (pintype "passive"))
      (node (ref "UC2") (pin "15") (pinfunction "PB1(OC1A)_15") (pintype "bidirectional"))
    )
    (net (code "55") (name "SCK") (class "Default")
      (node (ref "CON13") (pin "3") (pinfunction "3_3") (pintype "passive"))
      (node (ref "UC2") (pin "19") (pinfunction "PB5(SCK)_19") (pintype "bidirectional"))
    )
    (net (code "56") (name "SCL") (class "Default")
      (node (ref "CN3") (pin "4") (pinfunction "4_4") (pintype "bidirectional"))
      (node (ref "UC2") (pin "28") (pinfunction "PC5(ADC5/SCL)_28") (pintype "bidirectional"))
    )
    (net (code "57") (name "SDA") (class "Default")
      (node (ref "CN3") (pin "3") (pinfunction "3_3") (pintype "bidirectional"))
      (node (ref "UC2") (pin "27") (pinfunction "PC4(ADC4/SDA)_27") (pintype "bidirectional"))
    )
    (net (code "58") (name "TARE") (class "Default")
      (node (ref "PB4") (pin "1") (pinfunction "1_1") (pintype "passive"))
      (node (ref "PB4") (pin "2") (pinfunction "1_2") (pintype "passive"))
      (node (ref "R19") (pin "1") (pinfunction "1_1") (pintype "passive"))
      (node (ref "UC2") (pin "13") (pinfunction "PD7(AIN1)_13") (pintype "bidirectional"))
    )
    (net (code "59") (name "TX1") (class "Default")
      (node (ref "IC3") (pin "11") (pinfunction "DIN1_11") (pintype "bidirectional"))
      (node (ref "JP1") (pin "P$2") (pinfunction "TXO_P$2") (pintype "bidirectional"))
      (node (ref "UC2") (pin "3") (pinfunction "PD1(TXD)_3") (pintype "bidirectional"))
    )
    (net (code "60") (name "TX1_OUT") (class "Default")
      (node (ref "CON2") (pin "3") (pinfunction "3_3") (pintype "passive"))
      (node (ref "IC3") (pin "14") (pinfunction "DOUT1_14") (pintype "bidirectional"))
    )
    (net (code "61") (name "TX2") (class "Default")
      (node (ref "IC3") (pin "10") (pinfunction "DIN2_10") (pintype "bidirectional"))
    )
    (net (code "62") (name "TX2_OUT") (class "Default")
      (node (ref "IC3") (pin "7") (pinfunction "DOUT2_7") (pintype "bidirectional"))
    )
    (net (code "63") (name "TXD_LOG") (class "Default")
      (node (ref "R27") (pin "2") (pinfunction "2_2") (pintype "passive"))
      (node (ref "UC2") (pin "16") (pinfunction "PB2(SS/OC1B)_16") (pintype "bidirectional"))
    )
    (net (code "64") (name "TXD_LOG_3V3") (class "Default")
      (node (ref "MOD3") (pin "2") (pinfunction "RXI_2") (pintype "passive"))
      (node (ref "R12") (pin "2") (pinfunction "2_2") (pintype "passive"))
      (node (ref "R27") (pin "1") (pinfunction "1_1") (pintype "passive"))
    )
    (net (code "65") (name "unconnected-(CON1-SHIELD1-Pad9)") (class "Default")
      (node (ref "CON1") (pin "9") (pinfunction "SHIELD1_9") (pintype "passive"))
    )
    (net (code "66") (name "unconnected-(CON1-SHIELD2-Pad10)") (class "Default")
      (node (ref "CON1") (pin "10") (pinfunction "SHIELD2_10") (pintype "passive"))
    )
    (net (code "67") (name "unconnected-(CON2-Pad7)") (class "Default")
      (node (ref "CON2") (pin "7") (pinfunction "7_7") (pintype "passive"))
    )
    (net (code "68") (name "unconnected-(CON2-Pad8)") (class "Default")
      (node (ref "CON2") (pin "8") (pinfunction "8_8") (pintype "passive"))
    )
    (net (code "69") (name "unconnected-(CON2-SHIELD1-Pad9)") (class "Default")
      (node (ref "CON2") (pin "9") (pinfunction "SHIELD1_9") (pintype "passive"))
    )
    (net (code "70") (name "unconnected-(CON2-SHIELD2-Pad10)") (class "Default")
      (node (ref "CON2") (pin "10") (pinfunction "SHIELD2_10") (pintype "passive"))
    )
    (net (code "71") (name "unconnected-(CON9-Pad1)") (class "Default")
      (node (ref "CON9") (pin "1") (pinfunction "1_1") (pintype "passive"))
    )
    (net (code "72") (name "unconnected-(CON9-Pad2)") (class "Default")
      (node (ref "CON9") (pin "2") (pinfunction "2_2") (pintype "passive"))
    )
    (net (code "73") (name "unconnected-(CON9-Pad3)") (class "Default")
      (node (ref "CON9") (pin "3") (pinfunction "3_3") (pintype "passive"))
    )
    (net (code "74") (name "unconnected-(CON9-Pad4)") (class "Default")
      (node (ref "CON9") (pin "4") (pinfunction "4_4") (pintype "passive"))
    )
    (net (code "75") (name "unconnected-(CON9-Pad5)") (class "Default")
      (node (ref "CON9") (pin "5") (pinfunction "5_5") (pintype "passive"))
    )
    (net (code "76") (name "unconnected-(CON9-Pad6)") (class "Default")
      (node (ref "CON9") (pin "6") (pinfunction "6_6") (pintype "passive"))
    )
    (net (code "77") (name "unconnected-(CON9-Pad7)") (class "Default")
      (node (ref "CON9") (pin "7") (pinfunction "7_7") (pintype "passive"))
    )
    (net (code "78") (name "unconnected-(CON9-Pad8)") (class "Default")
      (node (ref "CON9") (pin "8") (pinfunction "8_8") (pintype "passive"))
    )
    (net (code "79") (name "unconnected-(CON10-Pad1)") (class "Default")
      (node (ref "CON10") (pin "1") (pinfunction "1_1") (pintype "passive"))
    )
    (net (code "80") (name "unconnected-(CON10-Pad2)") (class "Default")
      (node (ref "CON10") (pin "2") (pinfunction "2_2") (pintype "passive"))
    )
    (net (code "81") (name "unconnected-(CON10-Pad3)") (class "Default")
      (node (ref "CON10") (pin "3") (pinfunction "3_3") (pintype "passive"))
    )
    (net (code "82") (name "unconnected-(CON10-Pad4)") (class "Default")
      (node (ref "CON10") (pin "4") (pinfunction "4_4") (pintype "passive"))
    )
    (net (code "83") (name "unconnected-(CON10-Pad5)") (class "Default")
      (node (ref "CON10") (pin "5") (pinfunction "5_5") (pintype "passive"))
    )
    (net (code "84") (name "unconnected-(CON10-Pad6)") (class "Default")
      (node (ref "CON10") (pin "6") (pinfunction "6_6") (pintype "passive"))
    )
    (net (code "85") (name "unconnected-(CON10-Pad7)") (class "Default")
      (node (ref "CON10") (pin "7") (pinfunction "7_7") (pintype "passive"))
    )
    (net (code "86") (name "unconnected-(CON10-Pad8)") (class "Default")
      (node (ref "CON10") (pin "8") (pinfunction "8_8") (pintype "passive"))
    )
    (net (code "87") (name "unconnected-(CON11-Pad1)") (class "Default")
      (node (ref "CON11") (pin "1") (pinfunction "1_1") (pintype "passive"))
    )
    (net (code "88") (name "unconnected-(CON11-Pad2)") (class "Default")
      (node (ref "CON11") (pin "2") (pinfunction "2_2") (pintype "passive"))
    )
    (net (code "89") (name "unconnected-(CON11-Pad3)") (class "Default")
      (node (ref "CON11") (pin "3") (pinfunction "3_3") (pintype "passive"))
    )
    (net (code "90") (name "unconnected-(CON11-Pad4)") (class "Default")
      (node (ref "CON11") (pin "4") (pinfunction "4_4") (pintype "passive"))
    )
    (net (code "91") (name "unconnected-(CON11-Pad5)") (class "Default")
      (node (ref "CON11") (pin "5") (pinfunction "5_5") (pintype "passive"))
    )
    (net (code "92") (name "unconnected-(CON11-Pad6)") (class "Default")
      (node (ref "CON11") (pin "6") (pinfunction "6_6") (pintype "passive"))
    )
    (net (code "93") (name "unconnected-(CON11-Pad7)") (class "Default")
      (node (ref "CON11") (pin "7") (pinfunction "7_7") (pintype "passive"))
    )
    (net (code "94") (name "unconnected-(CON11-Pad8)") (class "Default")
      (node (ref "CON11") (pin "8") (pinfunction "8_8") (pintype "passive"))
    )
    (net (code "95") (name "unconnected-(IC2-ERROR'-Pad5)") (class "Default")
      (node (ref "IC2") (pin "5") (pinfunction "ERROR'_5") (pintype "bidirectional"))
    )
    (net (code "96") (name "unconnected-(IC4-NC-Pad6)") (class "Default")
      (node (ref "IC4") (pin "6") (pinfunction "NC_6") (pintype "bidirectional"))
    )
    (net (code "97") (name "unconnected-(JP1-CTS-PadP$5)") (class "Default")
      (node (ref "JP1") (pin "P$5") (pinfunction "CTS_P$5") (pintype "bidirectional"))
    )
    (net (code "98") (name "unconnected-(JP1-DTR-PadP$1)") (class "Default")
      (node (ref "JP1") (pin "P$1") (pinfunction "DTR_P$1") (pintype "bidirectional"))
    )
    (net (code "99") (name "unconnected-(MOD3-GRN-Pad1)") (class "Default")
      (node (ref "MOD3") (pin "1") (pinfunction "GRN_1") (pintype "passive"))
    )
  )
)
